# LCD_Display.net
KiCad netlist of a schematic drawn in Altium Designer
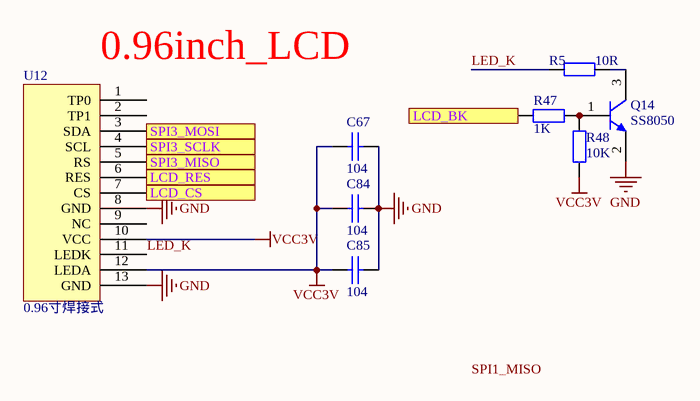
[diagram p0: LCD_Display.SchDoc]

(export (version "E")
  (design (tool "Eeschema 10.0.6"))
  (components
    (comp (ref "C67")
      (value "104")
      (footprint "0402C")
      (fields (field (name "Comment") "CAP"))
      (libsource (lib "MY SCH LIB__JCH") (part "CAP"))
    )
    (comp (ref "C84")
      (value "104")
      (footprint "0402C")
      (fields (field (name "Comment") "CAP"))
      (libsource (lib "MY SCH LIB__JCH") (part "CAP"))
    )
    (comp (ref "C85")
      (value "104")
      (footprint "0402C")
      (fields (field (name "Comment") "CAP"))
      (libsource (lib "MY SCH LIB__JCH") (part "CAP"))
    )
    (comp (ref "Q14")
      (value "SS8050")
      (footprint "SOT-23Q")
      (description "NPN贴片三极管")
      (fields (field (name "PUBLISHER") "Altium Limited"))
      (libsource (lib "SMC_Devices") (part "SS8050"))
    )
    (comp (ref "R5")
      (value "10R")
      (footprint "0402R")
      (description "Resistor")
      (libsource (lib "*") (part "RES"))
    )
    (comp (ref "R47")
      (value "1K")
      (footprint "0402R")
      (description "贴片电阻")
      (fields (field (name "Comment") "Res1") (field (name "PUBLISHER") "Altium Limited"))
      (libsource (lib "") (part "Res1_1"))
    )
    (comp (ref "R48")
      (value "10K")
      (footprint "0402R")
      (description "贴片电阻")
      (fields (field (name "Comment") "Res1") (field (name "PUBLISHER") "Altium Limited"))
      (libsource (lib "SMC_Devices") (part "Res1"))
    )
    (comp (ref "U12") (value "0.96寸焊接式") (footprint "13PIN-LCD") (libsource (lib "UAV") (part "0.96寸焊接式")))
  )
  (nets
    (net (code "1") (name "/LCD_BK") (class "Default")
      (node (ref "R47") (pin "1") (pinfunction "1_1") (pintype "passive"))
    )
    (net (code "2") (name "/LCD_CS") (class "Default")
      (node (ref "U12") (pin "7") (pinfunction "CS_7") (pintype "passive"))
    )
    (net (code "3") (name "/LCD_RES") (class "Default")
      (node (ref "U12") (pin "6") (pinfunction "RES_6") (pintype "passive"))
    )
    (net (code "4") (name "/LED_K") (class "Default")
      (node (ref "R5") (pin "1") (pinfunction "1_1") (pintype "passive"))
      (node (ref "U12") (pin "11") (pinfunction "LEDK_11") (pintype "passive"))
    )
    (net (code "6") (name "/SPI3_MISO") (class "Default")
      (node (ref "U12") (pin "5") (pinfunction "RS_5") (pintype "passive"))
    )
    (net (code "7") (name "/SPI3_MOSI") (class "Default")
      (node (ref "U12") (pin "3") (pinfunction "SDA_3") (pintype "passive"))
    )
    (net (code "8") (name "/SPI3_SCLK") (class "Default")
      (node (ref "U12") (pin "4") (pinfunction "SCL_4") (pintype "passive"))
    )
    (net (code "9") (name "GND") (class "Default")
      (node (ref "C67") (pin "2") (pinfunction "2_2") (pintype "passive"))
      (node (ref "C84") (pin "2") (pinfunction "2_2") (pintype "passive"))
      (node (ref "C85") (pin "2") (pinfunction "2_2") (pintype "passive"))
      (node (ref "Q14") (pin "2") (pinfunction "E_2") (pintype "passive"))
      (node (ref "U12") (pin "13") (pinfunction "GND_13") (pintype "passive"))
      (node (ref "U12") (pin "8") (pinfunction "GND_8") (pintype "passive"))
    )
    (net (code "10") (name "Net-(Q14-B)") (class "Default")
      (node (ref "Q14") (pin "1") (pinfunction "B_1") (pintype "passive"))
      (node (ref "R47") (pin "2") (pinfunction "2_2") (pintype "passive"))
      (node (ref "R48") (pin "2") (pinfunction "2_2") (pintype "passive"))
    )
    (net (code "11") (name "Net-(Q14-C)") (class "Default")
      (node (ref "Q14") (pin "3") (pinfunction "C_3") (pintype "passive"))
      (node (ref "R5") (pin "2") (pinfunction "2_2") (pintype "passive"))
    )
    (net (code "12") (name "VCC3V") (class "Default")
      (node (ref "C67") (pin "1") (pinfunction "1_1") (pintype "passive"))
      (node (ref "C84") (pin "1") (pinfunction "1_1") (pintype "passive"))
      (node (ref "C85") (pin "1") (pinfunction "1_1") (pintype "passive"))
      (node (ref "R48") (pin "1") (pinfunction "1_1") (pintype "passive"))
      (node (ref "U12") (pin "10") (pinfunction "VCC_10") (pintype "passive"))
      (node (ref "U12") (pin "12") (pinfunction "LEDA_12") (pintype "passive"))
    )
    (net (code "13") (name "unconnected-(U12-NC-Pad9)") (class "Default")
      (node (ref "U12") (pin "9") (pinfunction "NC_9") (pintype "passive"))
    )
    (net (code "14") (name "unconnected-(U12-TP0-Pad1)") (class "Default")
      (node (ref "U12") (pin "1") (pinfunction "TP0_1") (pintype "passive"))
    )
    (net (code "15") (name "unconnected-(U12-TP1-Pad2)") (class "Default")
      (node (ref "U12") (pin "2") (pinfunction "TP1_2") (pintype "passive"))
    )
  )
)
